# New_Action_Moteurs.net
KiCad netlist of a schematic drawn in Altium Designer
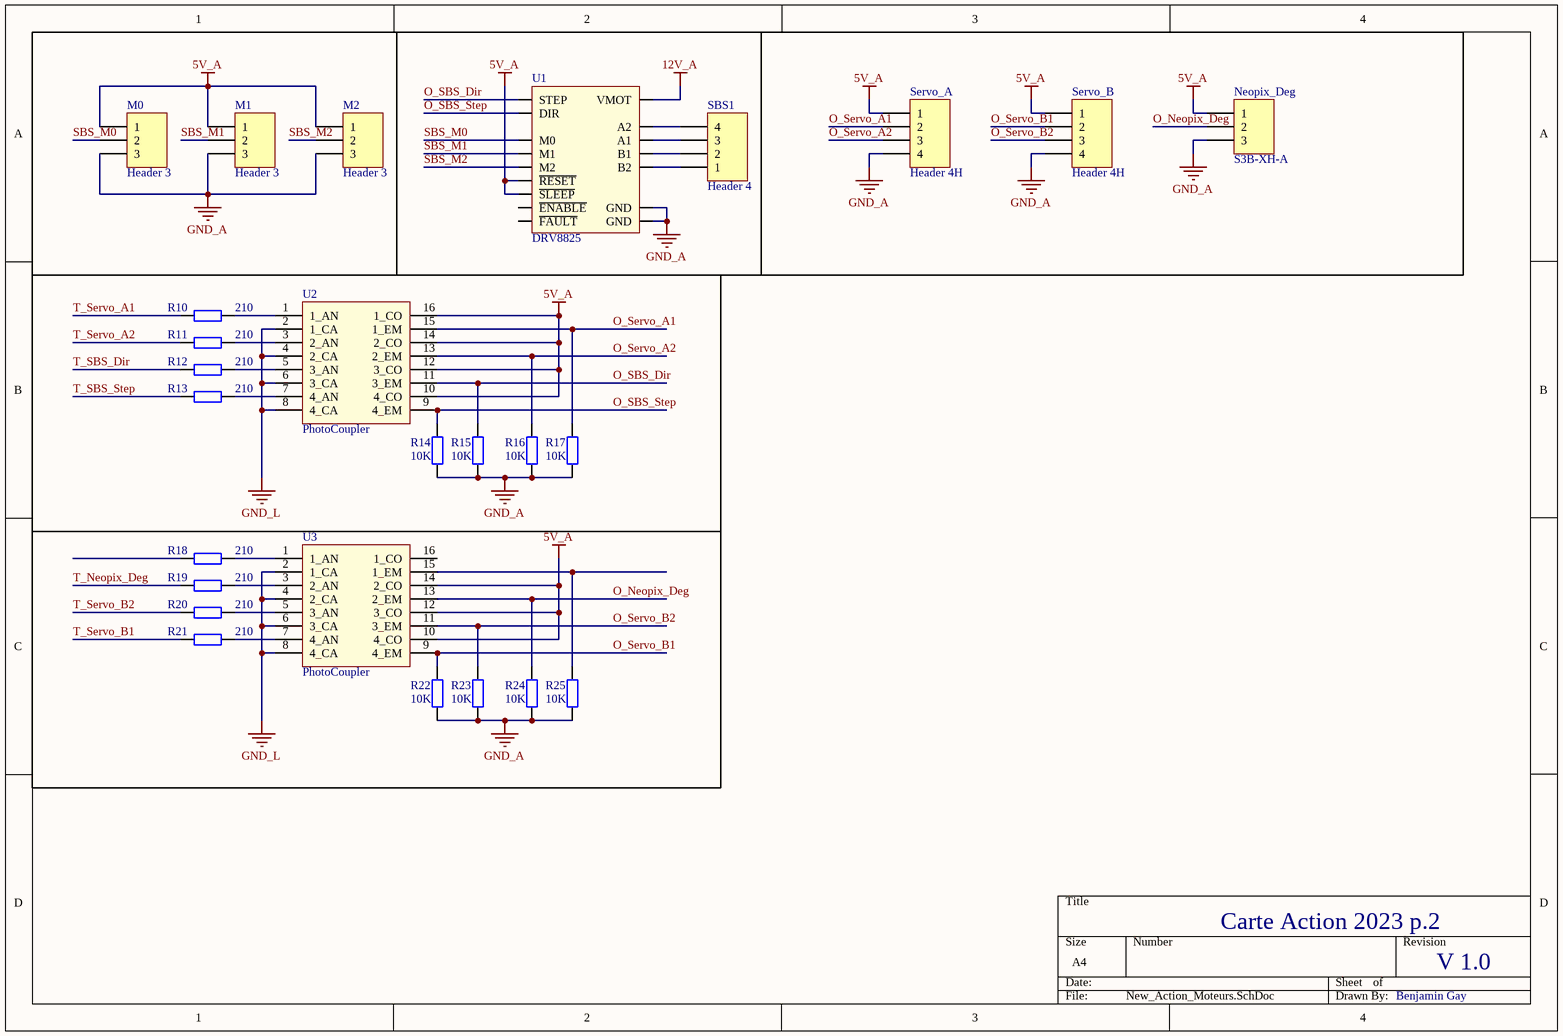
[diagram p0: New_Action_Moteurs.SchDoc]

(export (version "E")
  (design (tool "Eeschema 10.0.6"))
  (components
    (comp (ref "M0")
      (value "Header 3")
      (footprint "HDR1X3")
      (description "Header, 3-Pin")
      (fields (field (name "PUBLISHER") "Altium Limited"))
      (libsource (lib "Miscellaneous Connectors") (part "Header 3"))
    )
    (comp (ref "M1")
      (value "Header 3")
      (footprint "HDR1X3")
      (description "Header, 3-Pin")
      (fields (field (name "PUBLISHER") "Altium Limited"))
      (libsource (lib "Miscellaneous Connectors") (part "Header 3"))
    )
    (comp (ref "M2")
      (value "Header 3")
      (footprint "HDR1X3")
      (description "Header, 3-Pin")
      (fields (field (name "PUBLISHER") "Altium Limited"))
      (libsource (lib "Miscellaneous Connectors") (part "Header 3"))
    )
    (comp (ref "Neopix_Deg")
      (value "S3B-XH-A")
      (footprint "S3B-XH-A")
      (description "Header, 3-Pin, Right Angle")
      (fields (field (name "PUBLISHER") "Altium Limited"))
      (libsource (lib "Miscellaneous Connectors") (part "Header 3H"))
    )
    (comp (ref "R10")
      (value "210")
      (footprint "Resistor 1206")
      (description "Resistor")
      (fields (field (name "Comment") "Res2") (field (name "PUBLISHER") "Altium Limited"))
      (libsource (lib "") (part "Res2_1"))
    )
    (comp (ref "R11")
      (value "210")
      (footprint "Resistor 1206")
      (description "Resistor")
      (fields (field (name "Comment") "Res2") (field (name "PUBLISHER") "Altium Limited"))
      (libsource (lib "") (part "Res2_1"))
    )
    (comp (ref "R12")
      (value "210")
      (footprint "Resistor 1206")
      (description "Resistor")
      (fields (field (name "Comment") "Res2") (field (name "PUBLISHER") "Altium Limited"))
      (libsource (lib "") (part "Res2_1"))
    )
    (comp (ref "R13")
      (value "210")
      (footprint "Resistor 1206")
      (description "Resistor")
      (fields (field (name "Comment") "Res2") (field (name "PUBLISHER") "Altium Limited"))
      (libsource (lib "") (part "Res2_1"))
    )
    (comp (ref "R14")
      (value "10K")
      (footprint "Resistor 1206")
      (description "Resistor")
      (fields (field (name "Comment") "Res2") (field (name "PUBLISHER") "Altium Limited"))
      (libsource (lib "Miscellaneous Devices") (part "Res2"))
    )
    (comp (ref "R15")
      (value "10K")
      (footprint "Resistor 1206")
      (description "Resistor")
      (fields (field (name "Comment") "Res2") (field (name "PUBLISHER") "Altium Limited"))
      (libsource (lib "Miscellaneous Devices") (part "Res2"))
    )
    (comp (ref "R16")
      (value "10K")
      (footprint "Resistor 1206")
      (description "Resistor")
      (fields (field (name "Comment") "Res2") (field (name "PUBLISHER") "Altium Limited"))
      (libsource (lib "Miscellaneous Devices") (part "Res2"))
    )
    (comp (ref "R17")
      (value "10K")
      (footprint "Resistor 1206")
      (description "Resistor")
      (fields (field (name "Comment") "Res2") (field (name "PUBLISHER") "Altium Limited"))
      (libsource (lib "Miscellaneous Devices") (part "Res2"))
    )
    (comp (ref "R18")
      (value "210")
      (footprint "Resistor 1206")
      (description "Resistor")
      (fields (field (name "Comment") "Res2") (field (name "PUBLISHER") "Altium Limited"))
      (libsource (lib "") (part "Res2_1"))
    )
    (comp (ref "R19")
      (value "210")
      (footprint "Resistor 1206")
      (description "Resistor")
      (fields (field (name "Comment") "Res2") (field (name "PUBLISHER") "Altium Limited"))
      (libsource (lib "") (part "Res2_1"))
    )
    (comp (ref "R20")
      (value "210")
      (footprint "Resistor 1206")
      (description "Resistor")
      (fields (field (name "Comment") "Res2") (field (name "PUBLISHER") "Altium Limited"))
      (libsource (lib "") (part "Res2_1"))
    )
    (comp (ref "R21")
      (value "210")
      (footprint "Resistor 1206")
      (description "Resistor")
      (fields (field (name "Comment") "Res2") (field (name "PUBLISHER") "Altium Limited"))
      (libsource (lib "") (part "Res2_1"))
    )
    (comp (ref "R22")
      (value "10K")
      (footprint "Resistor 1206")
      (description "Resistor")
      (fields (field (name "Comment") "Res2") (field (name "PUBLISHER") "Altium Limited"))
      (libsource (lib "Miscellaneous Devices") (part "Res2"))
    )
    (comp (ref "R23")
      (value "10K")
      (footprint "Resistor 1206")
      (description "Resistor")
      (fields (field (name "Comment") "Res2") (field (name "PUBLISHER") "Altium Limited"))
      (libsource (lib "Miscellaneous Devices") (part "Res2"))
    )
    (comp (ref "R24")
      (value "10K")
      (footprint "Resistor 1206")
      (description "Resistor")
      (fields (field (name "Comment") "Res2") (field (name "PUBLISHER") "Altium Limited"))
      (libsource (lib "Miscellaneous Devices") (part "Res2"))
    )
    (comp (ref "R25")
      (value "10K")
      (footprint "Resistor 1206")
      (description "Resistor")
      (fields (field (name "Comment") "Res2") (field (name "PUBLISHER") "Altium Limited"))
      (libsource (lib "Miscellaneous Devices") (part "Res2"))
    )
    (comp (ref "SBS1")
      (value "Header 4")
      (footprint "S4B-XH-A")
      (description "Header, 4-Pin")
      (fields (field (name "PUBLISHER") "Altium Limited"))
      (libsource (lib "Miscellaneous Connectors") (part "Header 4"))
    )
    (comp (ref "Servo_A")
      (value "Header 4H")
      (footprint "S4B-XH-A")
      (description "Header, 4-Pin, Right Angle")
      (fields (field (name "PUBLISHER") "Altium Limited"))
      (libsource (lib "Miscellaneous Connectors") (part "Header 4H"))
    )
    (comp (ref "Servo_B")
      (value "Header 4H")
      (footprint "S4B-XH-A")
      (description "Header, 4-Pin, Right Angle")
      (fields (field (name "PUBLISHER") "Altium Limited"))
      (libsource (lib "Miscellaneous Connectors") (part "Header 4H"))
    )
    (comp (ref "U1")
      (value "DRV8825")
      (footprint "DRV8825")
      (description "Stepper Driver Module")
      (libsource (lib "SupaeroRobot") (part "DRV8825"))
    )
    (comp (ref "U2")
      (value "PhotoCoupler")
      (footprint "16 pins SOIC, TI")
      (description "Integrated Circuit")
      (fields
        (field (name "MANUFACTURER_PART_NUMBER") "LTV-247")
        (field (name "MOUSER PART NUMBER") "859-LTV-247")
      )
      (libsource (lib "SamacSys") (part "LTV-247"))
    )
    (comp (ref "U3")
      (value "PhotoCoupler")
      (footprint "16 pins SOIC, TI")
      (description "Integrated Circuit")
      (fields
        (field (name "MANUFACTURER_PART_NUMBER") "LTV-247")
        (field (name "MOUSER PART NUMBER") "859-LTV-247")
      )
      (libsource (lib "SamacSys") (part "LTV-247"))
    )
  )
  (nets
    (net (code "1") (name "/O_Neopix_Deg") (class "Default")
      (node (ref "Neopix_Deg") (pin "2") (pinfunction "2_2") (pintype "passive"))
      (node (ref "R24") (pin "2") (pinfunction "2_2") (pintype "passive"))
      (node (ref "U3") (pin "13") (pinfunction "2_EM_13") (pintype "passive"))
    )
    (net (code "2") (name "/O_SBS_Dir") (class "Default")
      (node (ref "R15") (pin "2") (pinfunction "2_2") (pintype "passive"))
      (node (ref "U1") (pin "7") (pinfunction "STEP_7") (pintype "passive"))
      (node (ref "U2") (pin "11") (pinfunction "3_EM_11") (pintype "passive"))
    )
    (net (code "3") (name "/O_SBS_Step") (class "Default")
      (node (ref "R14") (pin "2") (pinfunction "2_2") (pintype "passive"))
      (node (ref "U1") (pin "8") (pinfunction "DIR_8") (pintype "passive"))
      (node (ref "U2") (pin "9") (pinfunction "4_EM_9") (pintype "passive"))
    )
    (net (code "4") (name "/O_Servo_A1") (class "Default")
      (node (ref "R17") (pin "2") (pinfunction "2_2") (pintype "passive"))
      (node (ref "Servo_A") (pin "2") (pinfunction "2_2") (pintype "passive"))
      (node (ref "U2") (pin "15") (pinfunction "1_EM_15") (pintype "passive"))
    )
    (net (code "5") (name "/O_Servo_A2") (class "Default")
      (node (ref "R16") (pin "2") (pinfunction "2_2") (pintype "passive"))
      (node (ref "Servo_A") (pin "3") (pinfunction "3_3") (pintype "passive"))
      (node (ref "U2") (pin "13") (pinfunction "2_EM_13") (pintype "passive"))
    )
    (net (code "6") (name "/O_Servo_B1") (class "Default")
      (node (ref "R22") (pin "2") (pinfunction "2_2") (pintype "passive"))
      (node (ref "Servo_B") (pin "2") (pinfunction "2_2") (pintype "passive"))
      (node (ref "U3") (pin "9") (pinfunction "4_EM_9") (pintype "passive"))
    )
    (net (code "7") (name "/O_Servo_B2") (class "Default")
      (node (ref "R23") (pin "2") (pinfunction "2_2") (pintype "passive"))
      (node (ref "Servo_B") (pin "3") (pinfunction "3_3") (pintype "passive"))
      (node (ref "U3") (pin "11") (pinfunction "3_EM_11") (pintype "passive"))
    )
    (net (code "8") (name "/SBS_M0") (class "Default")
      (node (ref "M0") (pin "2") (pinfunction "2_2") (pintype "passive"))
      (node (ref "U1") (pin "2") (pinfunction "M0_2") (pintype "passive"))
    )
    (net (code "9") (name "/SBS_M1") (class "Default")
      (node (ref "M1") (pin "2") (pinfunction "2_2") (pintype "passive"))
      (node (ref "U1") (pin "3") (pinfunction "M1_3") (pintype "passive"))
    )
    (net (code "10") (name "/SBS_M2") (class "Default")
      (node (ref "M2") (pin "2") (pinfunction "2_2") (pintype "passive"))
      (node (ref "U1") (pin "4") (pinfunction "M2_4") (pintype "passive"))
    )
    (net (code "11") (name "/T_Neopix_Deg") (class "Default")
      (node (ref "R19") (pin "2") (pinfunction "2_2") (pintype "passive"))
    )
    (net (code "12") (name "/T_SBS_Dir") (class "Default")
      (node (ref "R12") (pin "2") (pinfunction "2_2") (pintype "passive"))
    )
    (net (code "13") (name "/T_SBS_Step") (class "Default")
      (node (ref "R13") (pin "2") (pinfunction "2_2") (pintype "passive"))
    )
    (net (code "14") (name "/T_Servo_A1") (class "Default")
      (node (ref "R10") (pin "2") (pinfunction "2_2") (pintype "passive"))
    )
    (net (code "15") (name "/T_Servo_A2") (class "Default")
      (node (ref "R11") (pin "2") (pinfunction "2_2") (pintype "passive"))
    )
    (net (code "16") (name "/T_Servo_B1") (class "Default")
      (node (ref "R21") (pin "2") (pinfunction "2_2") (pintype "passive"))
    )
    (net (code "17") (name "/T_Servo_B2") (class "Default")
      (node (ref "R20") (pin "2") (pinfunction "2_2") (pintype "passive"))
    )
    (net (code "18") (name "5V_A") (class "Default")
      (node (ref "M0") (pin "1") (pinfunction "1_1") (pintype "passive"))
      (node (ref "M1") (pin "1") (pinfunction "1_1") (pintype "passive"))
      (node (ref "M2") (pin "1") (pinfunction "1_1") (pintype "passive"))
      (node (ref "Neopix_Deg") (pin "1") (pinfunction "1_1") (pintype "passive"))
      (node (ref "Servo_A") (pin "1") (pinfunction "1_1") (pintype "passive"))
      (node (ref "Servo_B") (pin "1") (pinfunction "1_1") (pintype "passive"))
      (node (ref "U1") (pin "5") (pinfunction "~{RESET}_5") (pintype "passive"))
      (node (ref "U1") (pin "6") (pinfunction "~{SLEEP}_6") (pintype "passive"))
      (node (ref "U2") (pin "10") (pinfunction "4_CO_10") (pintype "passive"))
      (node (ref "U2") (pin "12") (pinfunction "3_CO_12") (pintype "passive"))
      (node (ref "U2") (pin "14") (pinfunction "2_CO_14") (pintype "passive"))
      (node (ref "U2") (pin "16") (pinfunction "1_CO_16") (pintype "passive"))
      (node (ref "U3") (pin "10") (pinfunction "4_CO_10") (pintype "passive"))
      (node (ref "U3") (pin "12") (pinfunction "3_CO_12") (pintype "passive"))
      (node (ref "U3") (pin "14") (pinfunction "2_CO_14") (pintype "passive"))
    )
    (net (code "19") (name "12V_A") (class "Default")
      (node (ref "U1") (pin "16") (pinfunction "VMOT_16") (pintype "passive"))
    )
    (net (code "20") (name "GND_A") (class "Default")
      (node (ref "M0") (pin "3") (pinfunction "3_3") (pintype "passive"))
      (node (ref "M1") (pin "3") (pinfunction "3_3") (pintype "passive"))
      (node (ref "M2") (pin "3") (pinfunction "3_3") (pintype "passive"))
      (node (ref "Neopix_Deg") (pin "3") (pinfunction "3_3") (pintype "passive"))
      (node (ref "R14") (pin "1") (pinfunction "1_1") (pintype "passive"))
      (node (ref "R15") (pin "1") (pinfunction "1_1") (pintype "passive"))
      (node (ref "R16") (pin "1") (pinfunction "1_1") (pintype "passive"))
      (node (ref "R17") (pin "1") (pinfunction "1_1") (pintype "passive"))
      (node (ref "R22") (pin "1") (pinfunction "1_1") (pintype "passive"))
      (node (ref "R23") (pin "1") (pinfunction "1_1") (pintype "passive"))
      (node (ref "R24") (pin "1") (pinfunction "1_1") (pintype "passive"))
      (node (ref "R25") (pin "1") (pinfunction "1_1") (pintype "passive"))
      (node (ref "Servo_A") (pin "4") (pinfunction "4_4") (pintype "passive"))
      (node (ref "Servo_B") (pin "4") (pinfunction "4_4") (pintype "passive"))
      (node (ref "U1") (pin "15") (pinfunction "GND_15") (pintype "passive"))
      (node (ref "U1") (pin "9") (pinfunction "GND_9") (pintype "passive"))
    )
    (net (code "21") (name "GND_L") (class "Default")
      (node (ref "U2") (pin "2") (pinfunction "1_CA_2") (pintype "passive"))
      (node (ref "U2") (pin "4") (pinfunction "2_CA_4") (pintype "passive"))
      (node (ref "U2") (pin "6") (pinfunction "3_CA_6") (pintype "passive"))
      (node (ref "U2") (pin "8") (pinfunction "4_CA_8") (pintype "passive"))
      (node (ref "U3") (pin "2") (pinfunction "1_CA_2") (pintype "passive"))
      (node (ref "U3") (pin "4") (pinfunction "2_CA_4") (pintype "passive"))
      (node (ref "U3") (pin "6") (pinfunction "3_CA_6") (pintype "passive"))
      (node (ref "U3") (pin "8") (pinfunction "4_CA_8") (pintype "passive"))
    )
    (net (code "22") (name "Net-(U1-A1)") (class "Default")
      (node (ref "SBS1") (pin "3") (pinfunction "3_3") (pintype "passive"))
      (node (ref "U1") (pin "12") (pinfunction "A1_12") (pintype "passive"))
    )
    (net (code "23") (name "Net-(U1-A2)") (class "Default")
      (node (ref "SBS1") (pin "4") (pinfunction "4_4") (pintype "passive"))
      (node (ref "U1") (pin "11") (pinfunction "A2_11") (pintype "passive"))
    )
    (net (code "24") (name "Net-(U1-B1)") (class "Default")
      (node (ref "SBS1") (pin "2") (pinfunction "2_2") (pintype "passive"))
      (node (ref "U1") (pin "13") (pinfunction "B1_13") (pintype "passive"))
    )
    (net (code "25") (name "Net-(U1-B2)") (class "Default")
      (node (ref "SBS1") (pin "1") (pinfunction "1_1") (pintype "passive"))
      (node (ref "U1") (pin "14") (pinfunction "B2_14") (pintype "passive"))
    )
    (net (code "26") (name "Net-(U2-1_AN)") (class "Default")
      (node (ref "R10") (pin "1") (pinfunction "1_1") (pintype "passive"))
      (node (ref "U2") (pin "1") (pinfunction "1_AN_1") (pintype "passive"))
    )
    (net (code "27") (name "Net-(U2-2_AN)") (class "Default")
      (node (ref "R11") (pin "1") (pinfunction "1_1") (pintype "passive"))
      (node (ref "U2") (pin "3") (pinfunction "2_AN_3") (pintype "passive"))
    )
    (net (code "28") (name "Net-(U2-3_AN)") (class "Default")
      (node (ref "R12") (pin "1") (pinfunction "1_1") (pintype "passive"))
      (node (ref "U2") (pin "5") (pinfunction "3_AN_5") (pintype "passive"))
    )
    (net (code "29") (name "Net-(U2-4_AN)") (class "Default")
      (node (ref "R13") (pin "1") (pinfunction "1_1") (pintype "passive"))
      (node (ref "U2") (pin "7") (pinfunction "4_AN_7") (pintype "passive"))
    )
    (net (code "30") (name "Net-(U3-1_AN)") (class "Default")
      (node (ref "R18") (pin "1") (pinfunction "1_1") (pintype "passive"))
      (node (ref "U3") (pin "1") (pinfunction "1_AN_1") (pintype "passive"))
    )
    (net (code "31") (name "Net-(U3-1_EM)") (class "Default")
      (node (ref "R25") (pin "2") (pinfunction "2_2") (pintype "passive"))
      (node (ref "U3") (pin "15") (pinfunction "1_EM_15") (pintype "passive"))
    )
    (net (code "32") (name "Net-(U3-2_AN)") (class "Default")
      (node (ref "R19") (pin "1") (pinfunction "1_1") (pintype "passive"))
      (node (ref "U3") (pin "3") (pinfunction "2_AN_3") (pintype "passive"))
    )
    (net (code "33") (name "Net-(U3-3_AN)") (class "Default")
      (node (ref "R20") (pin "1") (pinfunction "1_1") (pintype "passive"))
      (node (ref "U3") (pin "5") (pinfunction "3_AN_5") (pintype "passive"))
    )
    (net (code "34") (name "Net-(U3-4_AN)") (class "Default")
      (node (ref "R21") (pin "1") (pinfunction "1_1") (pintype "passive"))
      (node (ref "U3") (pin "7") (pinfunction "4_AN_7") (pintype "passive"))
    )
    (net (code "35") (name "unconnected-(R18-Pad2)") (class "Default")
      (node (ref "R18") (pin "2") (pinfunction "2_2") (pintype "passive"))
    )
    (net (code "36") (name "unconnected-(U1-~{ENABLE}-Pad1)") (class "Default")
      (node (ref "U1") (pin "1") (pinfunction "~{ENABLE}_1") (pintype "passive"))
    )
    (net (code "37") (name "unconnected-(U1-~{FAULT}-Pad10)") (class "Default")
      (node (ref "U1") (pin "10") (pinfunction "~{FAULT}_10") (pintype "passive"))
    )
    (net (code "38") (name "unconnected-(U3-1_CO-Pad16)") (class "Default")
      (node (ref "U3") (pin "16") (pinfunction "1_CO_16") (pintype "passive"))
    )
  )
)
